# Power.net
KiCad netlist of a schematic drawn in Altium Designer
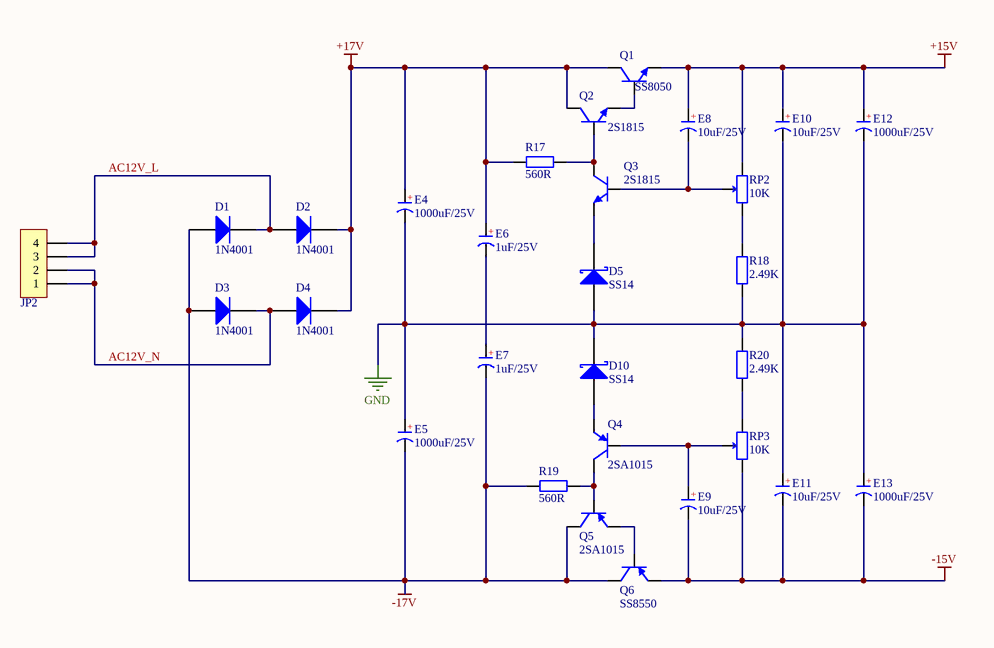
[diagram p0: Power.SchDoc]

(export (version "E")
  (design (tool "Eeschema 10.0.6"))
  (components
    (comp (ref "D1")
      (value "Diode")
      (footprint "DIODE-SMA")
      (description "二极管")
      (fields (field (name "TYPE") "1N4001") (field (name "PUBLISHER") "Altium Limited"))
      (libsource (lib "0.2 - 二极管-整流桥") (part "Diode"))
    )
    (comp (ref "D2")
      (value "Diode")
      (footprint "DIODE-SMA")
      (description "二极管")
      (fields (field (name "TYPE") "1N4001") (field (name "PUBLISHER") "Altium Limited"))
      (libsource (lib "0.2 - 二极管-整流桥") (part "Diode"))
    )
    (comp (ref "D3")
      (value "Diode")
      (footprint "DIODE-SMA")
      (description "二极管")
      (fields (field (name "TYPE") "1N4001") (field (name "PUBLISHER") "Altium Limited"))
      (libsource (lib "0.2 - 二极管-整流桥") (part "Diode"))
    )
    (comp (ref "D4")
      (value "Diode")
      (footprint "DIODE-SMA")
      (description "二极管")
      (fields (field (name "TYPE") "1N4001") (field (name "PUBLISHER") "Altium Limited"))
      (libsource (lib "0.2 - 二极管-整流桥") (part "Diode"))
    )
    (comp (ref "D5")
      (value "SS14")
      (footprint "SMA")
      (description "肖特基二极管")
      (libsource (lib "0.2 - 二极管-整流桥") (part "SS14"))
    )
    (comp (ref "D10")
      (value "SS14")
      (footprint "SMA")
      (description "肖特基二极管")
      (libsource (lib "0.2 - 二极管-整流桥") (part "SS14"))
    )
    (comp (ref "E4")
      (value "1000uF/25V")
      (footprint "CM G(12.5*13.5)")
      (description "贴片电解电容")
      (fields (field (name "版权归属") "封装库来自淘宝 ID：黄晶宝石"))
      (libsource (lib "0.1 - 电阻-电容-电感") (part "CE_SMD"))
    )
    (comp (ref "E5")
      (value "1000uF/25V")
      (footprint "CM G(12.5*13.5)")
      (description "贴片电解电容")
      (fields (field (name "版权归属") "封装库来自淘宝 ID：黄晶宝石"))
      (libsource (lib "0.1 - 电阻-电容-电感") (part "CE_SMD"))
    )
    (comp (ref "E6")
      (value "1uF/25V")
      (footprint "CD A(3216)")
      (description "贴片钽电容")
      (libsource (lib "0.1 - 电阻-电容-电感") (part "CT"))
    )
    (comp (ref "E7")
      (value "1uF/25V")
      (footprint "CD A(3216)")
      (description "贴片钽电容")
      (libsource (lib "0.1 - 电阻-电容-电感") (part "CT"))
    )
    (comp (ref "E8")
      (value "10uF/25V")
      (footprint "CM A(3*5.4)")
      (description "贴片电解电容")
      (fields (field (name "版权归属") "封装库来自淘宝 ID：黄晶宝石"))
      (libsource (lib "0.1 - 电阻-电容-电感") (part "CE_SMD"))
    )
    (comp (ref "E9")
      (value "10uF/25V")
      (footprint "CM A(3*5.4)")
      (description "贴片电解电容")
      (fields (field (name "版权归属") "封装库来自淘宝 ID：黄晶宝石"))
      (libsource (lib "0.1 - 电阻-电容-电感") (part "CE_SMD"))
    )
    (comp (ref "E10")
      (value "10uF/25V")
      (footprint "CD A(3216)")
      (description "贴片钽电容")
      (libsource (lib "0.1 - 电阻-电容-电感") (part "CT"))
    )
    (comp (ref "E11")
      (value "10uF/25V")
      (footprint "CD A(3216)")
      (description "贴片钽电容")
      (libsource (lib "0.1 - 电阻-电容-电感") (part "CT"))
    )
    (comp (ref "E12")
      (value "1000uF/25V")
      (footprint "CM G(12.5*13.5)")
      (description "贴片电解电容")
      (fields (field (name "版权归属") "封装库来自淘宝 ID：黄晶宝石"))
      (libsource (lib "0.1 - 电阻-电容-电感") (part "CE_SMD"))
    )
    (comp (ref "E13")
      (value "1000uF/25V")
      (footprint "CM G(12.5*13.5)")
      (description "贴片电解电容")
      (fields (field (name "版权归属") "封装库来自淘宝 ID：黄晶宝石"))
      (libsource (lib "0.1 - 电阻-电容-电感") (part "CE_SMD"))
    )
    (comp (ref "JP2")
      (value "HDR-1X4")
      (footprint "PH2.0-WS-4P")
      (description "4P接插件")
      (libsource (lib "5.3 - 接插件-脚距2.0") (part "Header 4"))
    )
    (comp (ref "Q1")
      (value "SS8050")
      (footprint "SOT23-3N")
      (description "高频放大-NPN型")
      (fields (field (name "版权归属") "封装库来自淘宝 ID：黄晶宝石"))
      (libsource (lib "0.4 - 三极管") (part "8050-SMD"))
    )
    (comp (ref "Q2")
      (value "2S1815")
      (footprint "SOT23-3N")
      (description "高频放大-NPN型")
      (fields (field (name "版权归属") "封装库来自淘宝 ID：黄晶宝石"))
      (libsource (lib "0.4 - 三极管") (part "8050-SMD"))
    )
    (comp (ref "Q3")
      (value "2S1815")
      (footprint "SOT23-3N")
      (description "高频放大-NPN型")
      (fields (field (name "版权归属") "封装库来自淘宝 ID：黄晶宝石"))
      (libsource (lib "0.4 - 三极管") (part "8050-SMD"))
    )
    (comp (ref "Q4")
      (value "2SA1015")
      (footprint "SOT23-3N")
      (description "高频放大-PNP型")
      (fields (field (name "版权归属") "封装库来自淘宝 ID：黄晶宝石"))
      (libsource (lib "0.4 - 三极管") (part "8550-SMD"))
    )
    (comp (ref "Q5")
      (value "2SA1015")
      (footprint "SOT23-3N")
      (description "高频放大-PNP型")
      (fields (field (name "版权归属") "封装库来自淘宝 ID：黄晶宝石"))
      (libsource (lib "0.4 - 三极管") (part "8550-SMD"))
    )
    (comp (ref "Q6")
      (value "SS8550")
      (footprint "SOT23-3N")
      (description "高频放大-PNP型")
      (fields (field (name "版权归属") "封装库来自淘宝 ID：黄晶宝石"))
      (libsource (lib "0.4 - 三极管") (part "8550-SMD"))
    )
    (comp (ref "R17")
      (value "560R")
      (footprint "R 0603_L")
      (description "贴片电阻")
      (fields (field (name "版权归属") "来自淘宝 ID：黄晶宝石"))
      (libsource (lib "0.1 - 电阻-电容-电感") (part "R"))
    )
    (comp (ref "R18")
      (value "2.49K")
      (footprint "R 0603_L")
      (description "贴片电阻")
      (fields (field (name "版权归属") "来自淘宝 ID：黄晶宝石"))
      (libsource (lib "0.1 - 电阻-电容-电感") (part "R"))
    )
    (comp (ref "R19")
      (value "560R")
      (footprint "R 0603_L")
      (description "贴片电阻")
      (fields (field (name "版权归属") "来自淘宝 ID：黄晶宝石"))
      (libsource (lib "0.1 - 电阻-电容-电感") (part "R"))
    )
    (comp (ref "R20")
      (value "2.49K")
      (footprint "R 0603_L")
      (description "贴片电阻")
      (fields (field (name "版权归属") "来自淘宝 ID：黄晶宝石"))
      (libsource (lib "0.1 - 电阻-电容-电感") (part "R"))
    )
    (comp (ref "RP2")
      (value "10K")
      (footprint "3296W")
      (description "单联电位器")
      (fields (field (name "版权归属") "封装库来自淘宝 ID：黄晶宝石"))
      (libsource (lib "0.1 - 电阻-电容-电感") (part "RP"))
    )
    (comp (ref "RP3")
      (value "10K")
      (footprint "3296W")
      (description "单联电位器")
      (fields (field (name "版权归属") "封装库来自淘宝 ID：黄晶宝石"))
      (libsource (lib "0.1 - 电阻-电容-电感") (part "RP"))
    )
  )
  (nets
    (net (code "1") (name "+15V") (class "Default")
      (node (ref "E10") (pin "1") (pinfunction "A_1") (pintype "passive"))
      (node (ref "E12") (pin "1") (pinfunction "A_1") (pintype "passive"))
      (node (ref "E8") (pin "1") (pinfunction "A_1") (pintype "passive"))
      (node (ref "Q1") (pin "2") (pinfunction "E_2") (pintype "passive"))
      (node (ref "RP2") (pin "1") (pinfunction "1_1") (pintype "passive"))
    )
    (net (code "2") (name "+17V") (class "Default")
      (node (ref "D2") (pin "2") (pinfunction "K_2") (pintype "passive"))
      (node (ref "D4") (pin "2") (pinfunction "K_2") (pintype "passive"))
      (node (ref "E4") (pin "1") (pinfunction "A_1") (pintype "passive"))
      (node (ref "E6") (pin "1") (pinfunction "A_1") (pintype "passive"))
      (node (ref "Q1") (pin "3") (pinfunction "C_3") (pintype "passive"))
      (node (ref "Q2") (pin "3") (pinfunction "C_3") (pintype "passive"))
      (node (ref "R17") (pin "2") (pinfunction "2_2") (pintype "passive"))
    )
    (net (code "3") (name "-15V") (class "Default")
      (node (ref "E11") (pin "2") (pinfunction "K_2") (pintype "passive"))
      (node (ref "E13") (pin "2") (pinfunction "K_2") (pintype "passive"))
      (node (ref "E9") (pin "2") (pinfunction "K_2") (pintype "passive"))
      (node (ref "Q6") (pin "2") (pinfunction "E_2") (pintype "passive"))
      (node (ref "RP3") (pin "3") (pinfunction "3_3") (pintype "passive"))
    )
    (net (code "4") (name "-17V") (class "Default")
      (node (ref "D1") (pin "1") (pinfunction "A_1") (pintype "passive"))
      (node (ref "D3") (pin "1") (pinfunction "A_1") (pintype "passive"))
      (node (ref "E5") (pin "2") (pinfunction "K_2") (pintype "passive"))
      (node (ref "E7") (pin "2") (pinfunction "K_2") (pintype "passive"))
      (node (ref "Q5") (pin "3") (pinfunction "C_3") (pintype "passive"))
      (node (ref "Q6") (pin "3") (pinfunction "C_3") (pintype "passive"))
      (node (ref "R19") (pin "2") (pinfunction "2_2") (pintype "passive"))
    )
    (net (code "5") (name "GND") (class "Default")
      (node (ref "D10") (pin "2") (pinfunction "K_2") (pintype "passive"))
      (node (ref "D5") (pin "1") (pinfunction "A_1") (pintype "passive"))
      (node (ref "E10") (pin "2") (pinfunction "K_2") (pintype "passive"))
      (node (ref "E11") (pin "1") (pinfunction "A_1") (pintype "passive"))
      (node (ref "E12") (pin "2") (pinfunction "K_2") (pintype "passive"))
      (node (ref "E13") (pin "1") (pinfunction "A_1") (pintype "passive"))
      (node (ref "E4") (pin "2") (pinfunction "K_2") (pintype "passive"))
      (node (ref "E5") (pin "1") (pinfunction "A_1") (pintype "passive"))
      (node (ref "R18") (pin "1") (pinfunction "1_1") (pintype "passive"))
      (node (ref "R20") (pin "2") (pinfunction "2_2") (pintype "passive"))
    )
    (net (code "6") (name "Net-(D1-K)") (class "Default")
      (node (ref "D1") (pin "2") (pinfunction "K_2") (pintype "passive"))
      (node (ref "D2") (pin "1") (pinfunction "A_1") (pintype "passive"))
      (node (ref "JP2") (pin "3") (pinfunction "3_3") (pintype "passive"))
      (node (ref "JP2") (pin "4") (pinfunction "4_4") (pintype "passive"))
    )
    (net (code "7") (name "Net-(D3-K)") (class "Default")
      (node (ref "D3") (pin "2") (pinfunction "K_2") (pintype "passive"))
      (node (ref "D4") (pin "1") (pinfunction "A_1") (pintype "passive"))
      (node (ref "JP2") (pin "1") (pinfunction "1_1") (pintype "passive"))
      (node (ref "JP2") (pin "2") (pinfunction "2_2") (pintype "passive"))
    )
    (net (code "8") (name "Net-(D5-K)") (class "Default")
      (node (ref "D5") (pin "2") (pinfunction "K_2") (pintype "passive"))
      (node (ref "Q3") (pin "2") (pinfunction "E_2") (pintype "passive"))
    )
    (net (code "9") (name "Net-(D10-A)") (class "Default")
      (node (ref "D10") (pin "1") (pinfunction "A_1") (pintype "passive"))
      (node (ref "Q4") (pin "2") (pinfunction "E_2") (pintype "passive"))
    )
    (net (code "10") (name "Net-(E6-K)") (class "Default")
      (node (ref "E6") (pin "2") (pinfunction "K_2") (pintype "passive"))
      (node (ref "E7") (pin "1") (pinfunction "A_1") (pintype "passive"))
    )
    (net (code "11") (name "Net-(E8-K)") (class "Default")
      (node (ref "E8") (pin "2") (pinfunction "K_2") (pintype "passive"))
      (node (ref "Q3") (pin "1") (pinfunction "B_1") (pintype "passive"))
      (node (ref "RP2") (pin "2") (pinfunction "2_2") (pintype "passive"))
    )
    (net (code "12") (name "Net-(E9-A)") (class "Default")
      (node (ref "E9") (pin "1") (pinfunction "A_1") (pintype "passive"))
      (node (ref "Q4") (pin "1") (pinfunction "B_1") (pintype "passive"))
      (node (ref "RP3") (pin "2") (pinfunction "2_2") (pintype "passive"))
    )
    (net (code "13") (name "Net-(Q1-B)") (class "Default")
      (node (ref "Q1") (pin "1") (pinfunction "B_1") (pintype "passive"))
      (node (ref "Q2") (pin "2") (pinfunction "E_2") (pintype "passive"))
    )
    (net (code "14") (name "Net-(Q2-B)") (class "Default")
      (node (ref "Q2") (pin "1") (pinfunction "B_1") (pintype "passive"))
      (node (ref "Q3") (pin "3") (pinfunction "C_3") (pintype "passive"))
      (node (ref "R17") (pin "1") (pinfunction "1_1") (pintype "passive"))
    )
    (net (code "15") (name "Net-(Q4-C)") (class "Default")
      (node (ref "Q4") (pin "3") (pinfunction "C_3") (pintype "passive"))
      (node (ref "Q5") (pin "1") (pinfunction "B_1") (pintype "passive"))
      (node (ref "R19") (pin "1") (pinfunction "1_1") (pintype "passive"))
    )
    (net (code "16") (name "Net-(Q5-E)") (class "Default")
      (node (ref "Q5") (pin "2") (pinfunction "E_2") (pintype "passive"))
      (node (ref "Q6") (pin "1") (pinfunction "B_1") (pintype "passive"))
    )
    (net (code "17") (name "Net-(R18-Pad2)") (class "Default")
      (node (ref "R18") (pin "2") (pinfunction "2_2") (pintype "passive"))
      (node (ref "RP2") (pin "3") (pinfunction "3_3") (pintype "passive"))
    )
    (net (code "18") (name "Net-(R20-Pad1)") (class "Default")
      (node (ref "R20") (pin "1") (pinfunction "1_1") (pintype "passive"))
      (node (ref "RP3") (pin "1") (pinfunction "1_1") (pintype "passive"))
    )
  )
)
